# F100C4T6B.net
KiCad netlist of a schematic drawn in Altium Designer
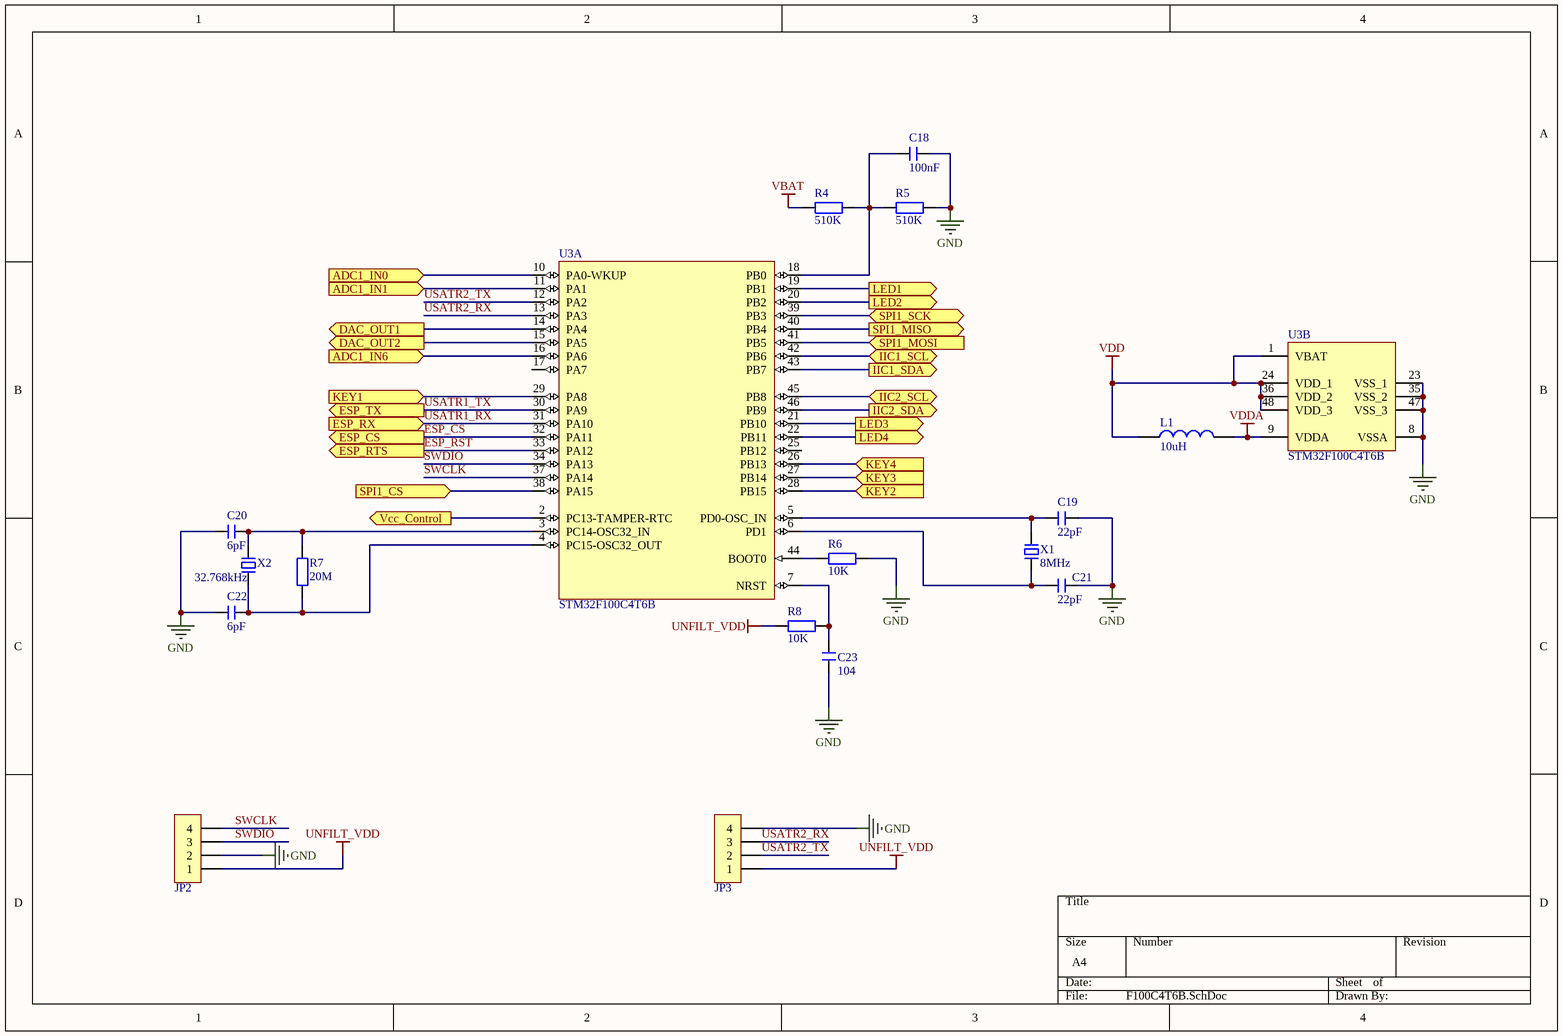
[diagram p0: F100C4T6B.SchDoc]

(export (version "E")
  (design (tool "Eeschema 10.0.6"))
  (components
    (comp (ref "C18")
      (value "100nF")
      (footprint "C 0603_L")
      (description "贴片电容")
      (libsource (lib "0.1 - 电阻-电容-电感") (part "C"))
    )
    (comp (ref "C19")
      (value "22pF")
      (footprint "C 0603_L")
      (description "贴片电容")
      (libsource (lib "0.1 - 电阻-电容-电感") (part "C"))
    )
    (comp (ref "C20")
      (value "6pF")
      (footprint "C 0603_L")
      (description "贴片电容")
      (libsource (lib "0.1 - 电阻-电容-电感") (part "C"))
    )
    (comp (ref "C21")
      (value "22pF")
      (footprint "C 0603_L")
      (description "贴片电容")
      (libsource (lib "0.1 - 电阻-电容-电感") (part "C"))
    )
    (comp (ref "C22")
      (value "6pF")
      (footprint "C 0603_L")
      (description "贴片电容")
      (libsource (lib "0.1 - 电阻-电容-电感") (part "C"))
    )
    (comp (ref "C23")
      (value "104")
      (footprint "C 0603_L")
      (description "贴片电容")
      (libsource (lib "0.1 - 电阻-电容-电感") (part "C"))
    )
    (comp (ref "JP2")
      (value "HDR-1X4")
      (footprint "HDR2.54-LI-4P")
      (description "4P接插件")
      (fields (field (name "版权归属") "封装库来自淘宝 ID：黄晶宝石"))
      (libsource (lib "5.4 - 接插件-脚距2.54 (100mil) ") (part "Header 4"))
    )
    (comp (ref "JP3")
      (value "HDR-1X4")
      (footprint "HDR2.54-LI-4P")
      (description "4P接插件")
      (fields (field (name "版权归属") "封装库来自淘宝 ID：黄晶宝石"))
      (libsource (lib "5.4 - 接插件-脚距2.54 (100mil) ") (part "Header 4"))
    )
    (comp (ref "L1")
      (value "10uH")
      (footprint "L 0805")
      (description "小功率贴片电感")
      (libsource (lib "0.1 - 电阻-电容-电感") (part "L"))
    )
    (comp (ref "R4")
      (value "510K")
      (footprint "R 0603_L")
      (description "贴片电阻")
      (fields (field (name "版权归属") "来自淘宝 ID：黄晶宝石"))
      (libsource (lib "0.1 - 电阻-电容-电感") (part "R"))
    )
    (comp (ref "R5")
      (value "510K")
      (footprint "R 0603_L")
      (description "贴片电阻")
      (fields (field (name "版权归属") "来自淘宝 ID：黄晶宝石"))
      (libsource (lib "0.1 - 电阻-电容-电感") (part "R"))
    )
    (comp (ref "R6")
      (value "10K")
      (footprint "R 0603_L")
      (description "贴片电阻")
      (fields (field (name "版权归属") "来自淘宝 ID：黄晶宝石"))
      (libsource (lib "0.1 - 电阻-电容-电感") (part "R"))
    )
    (comp (ref "R7")
      (value "20M")
      (footprint "R 0603_L")
      (description "贴片电阻")
      (fields (field (name "版权归属") "来自淘宝 ID：黄晶宝石"))
      (libsource (lib "0.1 - 电阻-电容-电感") (part "R"))
    )
    (comp (ref "R8")
      (value "10K")
      (footprint "R 0603_L")
      (description "贴片电阻")
      (fields (field (name "版权归属") "来自淘宝 ID：黄晶宝石"))
      (libsource (lib "0.1 - 电阻-电容-电感") (part "R"))
    )
    (comp (ref "U3")
      (value "STM32F100C4T6B")
      (footprint "LQFP48_N")
      (libsource (lib "2.3 - STM32 F1系列单片机") (part "STM32F100C4T6B"))
    )
    (comp (ref "X1")
      (value "8MHz")
      (footprint "OSC 5032-2P")
      (description "2脚无源脚晶振")
      (fields (field (name "版权归属") "封装库来自淘宝卖家 ID：黄晶宝石"))
      (libsource (lib "2.0 - 保险丝-晶振-光耦") (part "XTAL-2P"))
    )
    (comp (ref "X2")
      (value "32.768kHz")
      (footprint "OSC 3215-2P")
      (description "2脚无源脚晶振")
      (fields (field (name "版权归属") "封装库来自淘宝卖家 ID：黄晶宝石"))
      (libsource (lib "2.0 - 保险丝-晶振-光耦") (part "XTAL-2P"))
    )
  )
  (nets
    (net (code "1") (name "/ADC1_IN0") (class "Default")
      (node (ref "U3") (pin "10") (pinfunction "PA0-WKUP_10") (pintype "bidirectional"))
    )
    (net (code "2") (name "/ADC1_IN1") (class "Default")
      (node (ref "U3") (pin "11") (pinfunction "PA1_11") (pintype "bidirectional"))
    )
    (net (code "3") (name "/ADC1_IN6") (class "Default")
      (node (ref "U3") (pin "16") (pinfunction "PA6_16") (pintype "bidirectional"))
    )
    (net (code "4") (name "/DAC_OUT1") (class "Default")
      (node (ref "U3") (pin "14") (pinfunction "PA4_14") (pintype "bidirectional"))
    )
    (net (code "5") (name "/DAC_OUT2") (class "Default")
      (node (ref "U3") (pin "15") (pinfunction "PA5_15") (pintype "bidirectional"))
    )
    (net (code "6") (name "/ESP_CS") (class "Default")
      (node (ref "U3") (pin "32") (pinfunction "PA11_32") (pintype "bidirectional"))
    )
    (net (code "7") (name "/ESP_RTS") (class "Default")
      (node (ref "U3") (pin "33") (pinfunction "PA12_33") (pintype "bidirectional"))
    )
    (net (code "8") (name "/IIC1_SCL") (class "Default")
      (node (ref "U3") (pin "42") (pinfunction "PB6_42") (pintype "bidirectional"))
    )
    (net (code "9") (name "/IIC1_SDA") (class "Default")
      (node (ref "U3") (pin "43") (pinfunction "PB7_43") (pintype "bidirectional"))
    )
    (net (code "10") (name "/IIC2_SCL") (class "Default")
      (node (ref "U3") (pin "45") (pinfunction "PB8_45") (pintype "bidirectional"))
    )
    (net (code "11") (name "/IIC2_SDA") (class "Default")
      (node (ref "U3") (pin "46") (pinfunction "PB9_46") (pintype "bidirectional"))
    )
    (net (code "12") (name "/KEY1") (class "Default")
      (node (ref "U3") (pin "29") (pinfunction "PA8_29") (pintype "bidirectional"))
    )
    (net (code "13") (name "/KEY2") (class "Default")
      (node (ref "U3") (pin "28") (pinfunction "PB15_28") (pintype "bidirectional"))
    )
    (net (code "14") (name "/KEY3") (class "Default")
      (node (ref "U3") (pin "27") (pinfunction "PB14_27") (pintype "bidirectional"))
    )
    (net (code "15") (name "/KEY4") (class "Default")
      (node (ref "U3") (pin "26") (pinfunction "PB13_26") (pintype "bidirectional"))
    )
    (net (code "16") (name "/LED1") (class "Default")
      (node (ref "U3") (pin "19") (pinfunction "PB1_19") (pintype "bidirectional"))
    )
    (net (code "17") (name "/LED2") (class "Default")
      (node (ref "U3") (pin "20") (pinfunction "PB2_20") (pintype "bidirectional"))
    )
    (net (code "18") (name "/LED3") (class "Default")
      (node (ref "U3") (pin "21") (pinfunction "PB10_21") (pintype "bidirectional"))
    )
    (net (code "19") (name "/LED4") (class "Default")
      (node (ref "U3") (pin "22") (pinfunction "PB11_22") (pintype "bidirectional"))
    )
    (net (code "20") (name "/SPI1_CS") (class "Default")
      (node (ref "U3") (pin "38") (pinfunction "PA15_38") (pintype "bidirectional"))
    )
    (net (code "21") (name "/SPI1_MISO") (class "Default")
      (node (ref "U3") (pin "40") (pinfunction "PB4_40") (pintype "bidirectional"))
    )
    (net (code "22") (name "/SPI1_MOSI") (class "Default")
      (node (ref "U3") (pin "41") (pinfunction "PB5_41") (pintype "bidirectional"))
    )
    (net (code "23") (name "/SPI1_SCK") (class "Default")
      (node (ref "U3") (pin "39") (pinfunction "PB3_39") (pintype "bidirectional"))
    )
    (net (code "24") (name "/SWCLK") (class "Default")
      (node (ref "JP2") (pin "4") (pinfunction "4_4") (pintype "passive"))
      (node (ref "U3") (pin "37") (pinfunction "PA14_37") (pintype "bidirectional"))
    )
    (net (code "25") (name "/SWDIO") (class "Default")
      (node (ref "JP2") (pin "3") (pinfunction "3_3") (pintype "passive"))
      (node (ref "U3") (pin "34") (pinfunction "PA13_34") (pintype "bidirectional"))
    )
    (net (code "26") (name "/USATR1_RX") (class "Default")
      (node (ref "U3") (pin "31") (pinfunction "PA10_31") (pintype "bidirectional"))
    )
    (net (code "27") (name "/USATR1_TX") (class "Default")
      (node (ref "U3") (pin "30") (pinfunction "PA9_30") (pintype "bidirectional"))
    )
    (net (code "28") (name "/USATR2_RX") (class "Default")
      (node (ref "JP3") (pin "3") (pinfunction "3_3") (pintype "passive"))
      (node (ref "U3") (pin "13") (pinfunction "PA3_13") (pintype "bidirectional"))
    )
    (net (code "29") (name "/USATR2_TX") (class "Default")
      (node (ref "JP3") (pin "2") (pinfunction "2_2") (pintype "passive"))
      (node (ref "U3") (pin "12") (pinfunction "PA2_12") (pintype "bidirectional"))
    )
    (net (code "30") (name "/Vcc_Control") (class "Default")
      (node (ref "U3") (pin "2") (pinfunction "PC13-TAMPER-RTC_2") (pintype "bidirectional"))
    )
    (net (code "31") (name "GND") (class "Default")
      (node (ref "C18") (pin "1") (pinfunction "1_1") (pintype "passive"))
      (node (ref "C19") (pin "2") (pinfunction "2_2") (pintype "passive"))
      (node (ref "C20") (pin "2") (pinfunction "2_2") (pintype "passive"))
      (node (ref "C21") (pin "2") (pinfunction "2_2") (pintype "passive"))
      (node (ref "C22") (pin "2") (pinfunction "2_2") (pintype "passive"))
      (node (ref "C23") (pin "1") (pinfunction "1_1") (pintype "passive"))
      (node (ref "JP2") (pin "2") (pinfunction "2_2") (pintype "passive"))
      (node (ref "JP3") (pin "4") (pinfunction "4_4") (pintype "passive"))
      (node (ref "R5") (pin "1") (pinfunction "1_1") (pintype "passive"))
      (node (ref "R6") (pin "2") (pinfunction "2_2") (pintype "passive"))
      (node (ref "U3") (pin "23") (pinfunction "VSS_1_23") (pintype "power_in"))
      (node (ref "U3") (pin "35") (pinfunction "VSS_2_35") (pintype "power_in"))
      (node (ref "U3") (pin "47") (pinfunction "VSS_3_47") (pintype "power_in"))
      (node (ref "U3") (pin "8") (pinfunction "VSSA_8") (pintype "power_in"))
    )
    (net (code "32") (name "Net-(U3A-BOOT0)") (class "Default")
      (node (ref "R6") (pin "1") (pinfunction "1_1") (pintype "passive"))
      (node (ref "U3") (pin "44") (pinfunction "BOOT0_44") (pintype "input"))
    )
    (net (code "33") (name "Net-(U3A-NRST)") (class "Default")
      (node (ref "C23") (pin "2") (pinfunction "2_2") (pintype "passive"))
      (node (ref "R8") (pin "1") (pinfunction "1_1") (pintype "passive"))
      (node (ref "U3") (pin "7") (pinfunction "NRST_7") (pintype "bidirectional"))
    )
    (net (code "34") (name "Net-(U3A-PB0)") (class "Default")
      (node (ref "C18") (pin "2") (pinfunction "2_2") (pintype "passive"))
      (node (ref "R4") (pin "1") (pinfunction "1_1") (pintype "passive"))
      (node (ref "R5") (pin "2") (pinfunction "2_2") (pintype "passive"))
      (node (ref "U3") (pin "18") (pinfunction "PB0_18") (pintype "bidirectional"))
    )
    (net (code "35") (name "Net-(U3A-PC14-OSC32_IN)") (class "Default")
      (node (ref "C20") (pin "1") (pinfunction "1_1") (pintype "passive"))
      (node (ref "R7") (pin "1") (pinfunction "1_1") (pintype "passive"))
      (node (ref "U3") (pin "3") (pinfunction "PC14-OSC32_IN_3") (pintype "bidirectional"))
      (node (ref "X2") (pin "1") (pinfunction "1_1") (pintype "passive"))
    )
    (net (code "36") (name "Net-(U3A-PC15-OSC32_OUT)") (class "Default")
      (node (ref "C22") (pin "1") (pinfunction "1_1") (pintype "passive"))
      (node (ref "R7") (pin "2") (pinfunction "2_2") (pintype "passive"))
      (node (ref "U3") (pin "4") (pinfunction "PC15-OSC32_OUT_4") (pintype "bidirectional"))
      (node (ref "X2") (pin "2") (pinfunction "2_2") (pintype "passive"))
    )
    (net (code "37") (name "Net-(U3A-PD0-OSC_IN)") (class "Default")
      (node (ref "C19") (pin "1") (pinfunction "1_1") (pintype "passive"))
      (node (ref "U3") (pin "5") (pinfunction "PD0-OSC_IN_5") (pintype "bidirectional"))
      (node (ref "X1") (pin "2") (pinfunction "2_2") (pintype "passive"))
    )
    (net (code "38") (name "Net-(U3A-PD1)") (class "Default")
      (node (ref "C21") (pin "1") (pinfunction "1_1") (pintype "passive"))
      (node (ref "U3") (pin "6") (pinfunction "PD1_6") (pintype "bidirectional"))
      (node (ref "X1") (pin "1") (pinfunction "1_1") (pintype "passive"))
    )
    (net (code "39") (name "UNFILT_VDD") (class "Default")
      (node (ref "JP2") (pin "1") (pinfunction "1_1") (pintype "passive"))
      (node (ref "JP3") (pin "1") (pinfunction "1_1") (pintype "passive"))
      (node (ref "R8") (pin "2") (pinfunction "2_2") (pintype "passive"))
    )
    (net (code "40") (name "VBAT") (class "Default")
      (node (ref "R4") (pin "2") (pinfunction "2_2") (pintype "passive"))
    )
    (net (code "41") (name "VDD") (class "Default")
      (node (ref "L1") (pin "1") (pinfunction "1_1") (pintype "passive"))
      (node (ref "U3") (pin "1") (pinfunction "VBAT_1") (pintype "power_in"))
      (node (ref "U3") (pin "24") (pinfunction "VDD_1_24") (pintype "power_in"))
      (node (ref "U3") (pin "36") (pinfunction "VDD_2_36") (pintype "power_in"))
      (node (ref "U3") (pin "48") (pinfunction "VDD_3_48") (pintype "power_in"))
    )
    (net (code "42") (name "VDDA") (class "Default")
      (node (ref "L1") (pin "2") (pinfunction "2_2") (pintype "passive"))
      (node (ref "U3") (pin "9") (pinfunction "VDDA_9") (pintype "power_in"))
    )
    (net (code "43") (name "unconnected-(U3A-PA7-Pad17)") (class "Default")
      (node (ref "U3") (pin "17") (pinfunction "PA7_17") (pintype "bidirectional"))
    )
    (net (code "44") (name "unconnected-(U3A-PB12-Pad25)") (class "Default")
      (node (ref "U3") (pin "25") (pinfunction "PB12_25") (pintype "bidirectional"))
    )
  )
)
